# rcvr003.net
KiCad netlist of a schematic drawn in EAGLE
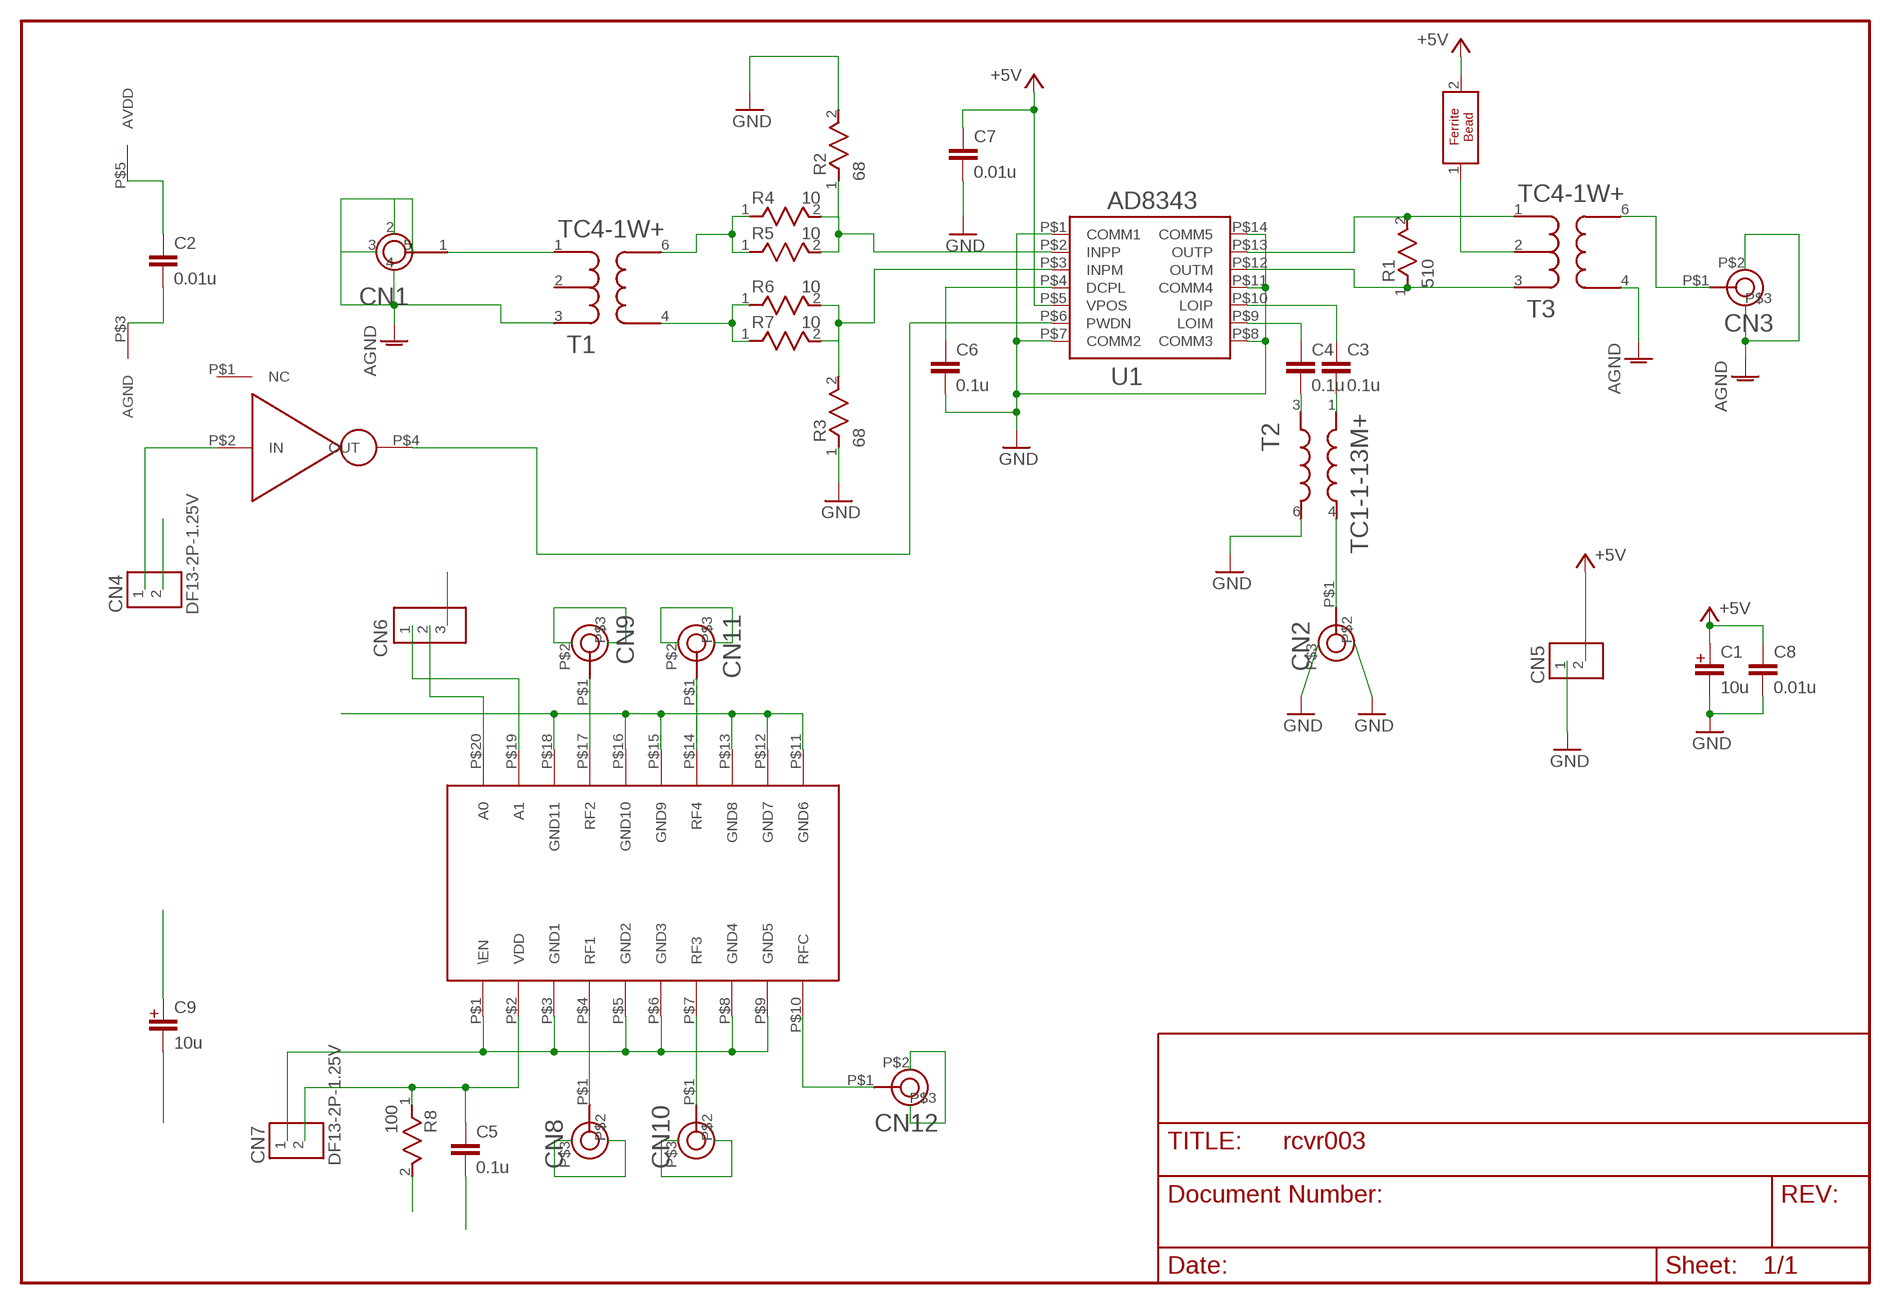
[diagram p0: schematic, sheet 1]

(export (version "E")
  (design (tool "Eeschema 10.0.6"))
  (components
    (comp (ref "C1")
      (value "10u")
      (footprint "eagle-import:3216_POLAR")
      (libsource (lib "eagle-import") (part "C_POLAR3216"))
    )
    (comp (ref "C2")
      (value "0.01u")
      (footprint "eagle-import:1005")
      (libsource (lib "eagle-import") (part "C1005"))
    )
    (comp (ref "C3")
      (value "0.1u")
      (footprint "eagle-import:1005")
      (libsource (lib "eagle-import") (part "C1005"))
    )
    (comp (ref "C4")
      (value "0.1u")
      (footprint "eagle-import:1005")
      (libsource (lib "eagle-import") (part "C1005"))
    )
    (comp (ref "C5")
      (value "0.1u")
      (footprint "eagle-import:1005")
      (libsource (lib "eagle-import") (part "C1005"))
    )
    (comp (ref "C6")
      (value "0.1u")
      (footprint "eagle-import:1005")
      (libsource (lib "eagle-import") (part "C1005"))
    )
    (comp (ref "C7")
      (value "0.01u")
      (footprint "eagle-import:1005")
      (libsource (lib "eagle-import") (part "C1005"))
    )
    (comp (ref "C8")
      (value "0.01u")
      (footprint "eagle-import:1608")
      (libsource (lib "eagle-import") (part "C1608"))
    )
    (comp (ref "C9")
      (value "10u")
      (footprint "eagle-import:3216_POLAR")
      (libsource (lib "eagle-import") (part "C_POLAR3216"))
    )
    (comp (ref "CN1")
      (value "SMASTRAIGHT")
      (footprint "eagle-import:SMA_STRAIGHT")
      (libsource (lib "eagle-import") (part "SMASTRAIGHT"))
    )
    (comp (ref "CN2")
      (value "U.FL-R-SMT")
      (footprint "eagle-import:U.FL-R-SMT")
      (libsource (lib "eagle-import") (part "U.FL-R-SMT"))
    )
    (comp (ref "CN3")
      (value "U.FL-R-SMT")
      (footprint "eagle-import:U.FL-R-SMT")
      (libsource (lib "eagle-import") (part "U.FL-R-SMT"))
    )
    (comp (ref "CN4")
      (value "DF13-2P-1.25V")
      (footprint "eagle-import:DF13-2P-12.5V")
      (libsource (lib "eagle-import") (part "DF13-2P-1.25V"))
    )
    (comp (ref "CN5")
      (value "DF13-2P-1.25V")
      (footprint "eagle-import:DF13-2P-12.5V")
      (libsource (lib "eagle-import") (part "DF13-2P-1.25V"))
    )
    (comp (ref "CN6")
      (value "DF13-3P-1.25V")
      (footprint "eagle-import:DF13-3P-1.25V")
      (libsource (lib "eagle-import") (part "DF13-3P-1.25V"))
    )
    (comp (ref "CN7")
      (value "DF13-2P-1.25V")
      (footprint "eagle-import:DF13-2P-12.5V")
      (libsource (lib "eagle-import") (part "DF13-2P-1.25V"))
    )
    (comp (ref "CN8")
      (value "U.FL-R-SMT")
      (footprint "eagle-import:U.FL-R-SMT")
      (libsource (lib "eagle-import") (part "U.FL-R-SMT"))
    )
    (comp (ref "CN9")
      (value "U.FL-R-SMT")
      (footprint "eagle-import:U.FL-R-SMT")
      (libsource (lib "eagle-import") (part "U.FL-R-SMT"))
    )
    (comp (ref "CN10")
      (value "U.FL-R-SMT")
      (footprint "eagle-import:U.FL-R-SMT")
      (libsource (lib "eagle-import") (part "U.FL-R-SMT"))
    )
    (comp (ref "CN11")
      (value "U.FL-R-SMT")
      (footprint "eagle-import:U.FL-R-SMT")
      (libsource (lib "eagle-import") (part "U.FL-R-SMT"))
    )
    (comp (ref "CN12")
      (value "U.FL-R-SMT")
      (footprint "eagle-import:U.FL-R-SMT")
      (libsource (lib "eagle-import") (part "U.FL-R-SMT"))
    )
    (comp (ref "FB2")
      (value "FERRITEBEAD")
      (footprint "eagle-import:1608")
      (libsource (lib "eagle-import") (part "FERRITEBEAD"))
    )
    (comp (ref "R1")
      (value "510")
      (footprint "eagle-import:1608")
      (libsource (lib "eagle-import") (part "R1608"))
    )
    (comp (ref "R2")
      (value "68")
      (footprint "eagle-import:1608")
      (libsource (lib "eagle-import") (part "R1608"))
    )
    (comp (ref "R3")
      (value "68")
      (footprint "eagle-import:1608")
      (libsource (lib "eagle-import") (part "R1608"))
    )
    (comp (ref "R4")
      (value "10")
      (footprint "eagle-import:1005")
      (libsource (lib "eagle-import") (part "R1005"))
    )
    (comp (ref "R5")
      (value "10")
      (footprint "eagle-import:1005")
      (libsource (lib "eagle-import") (part "R1005"))
    )
    (comp (ref "R6")
      (value "10")
      (footprint "eagle-import:1005")
      (libsource (lib "eagle-import") (part "R1005"))
    )
    (comp (ref "R7")
      (value "10")
      (footprint "eagle-import:1005")
      (libsource (lib "eagle-import") (part "R1005"))
    )
    (comp (ref "R8")
      (value "100")
      (footprint "eagle-import:1608")
      (libsource (lib "eagle-import") (part "R1608"))
    )
    (comp (ref "T1")
      (value "TC4-1W+")
      (footprint "eagle-import:AT224")
      (libsource (lib "eagle-import") (part "TC4-1W+"))
    )
    (comp (ref "T2")
      (value "TC1-1-13M+")
      (footprint "eagle-import:AT224")
      (libsource (lib "eagle-import") (part "TC1-1-13M+"))
    )
    (comp (ref "T3")
      (value "TC4-1W+")
      (footprint "eagle-import:AT224")
      (libsource (lib "eagle-import") (part "TC4-1W+"))
    )
    (comp (ref "U1")
      (value "AD8343")
      (footprint "eagle-import:AD8343")
      (libsource (lib "eagle-import") (part "AD8343"))
    )
    (comp (ref "U2")
      (value "MC74VHC1G04")
      (footprint "eagle-import:MC74VHC1G04")
      (libsource (lib "eagle-import") (part "MC74VHC1G04"))
    )
    (comp (ref "U3")
      (value "ADG904")
      (footprint "eagle-import:ADG904_TSSOP")
      (libsource (lib "eagle-import") (part "ADG904"))
    )
  )
  (nets
    (net (code "1") (name "+5V") (class "Default")
      (node (ref "C1") (pin "1") (pinfunction "1_1") (pintype "passive"))
      (node (ref "C2") (pin "1") (pinfunction "1_1") (pintype "passive"))
      (node (ref "C7") (pin "1") (pinfunction "1_1") (pintype "passive"))
      (node (ref "C8") (pin "1") (pinfunction "1_1") (pintype "passive"))
      (node (ref "CN5") (pin "2") (pinfunction "2_2") (pintype "bidirectional"))
      (node (ref "FB2") (pin "2") (pinfunction "P$4_2") (pintype "bidirectional"))
      (node (ref "U1") (pin "P$5") (pinfunction "VPOS_P$5") (pintype "power_in"))
      (node (ref "U2") (pin "P$5") (pinfunction "AVDD_P$5") (pintype "power_in"))
    )
    (net (code "2") (name "/3.3V") (class "Default")
      (node (ref "C5") (pin "1") (pinfunction "1_1") (pintype "passive"))
      (node (ref "C9") (pin "1") (pinfunction "1_1") (pintype "passive"))
      (node (ref "CN7") (pin "2") (pinfunction "2_2") (pintype "bidirectional"))
      (node (ref "R8") (pin "1") (pinfunction "1_1") (pintype "passive"))
      (node (ref "U3") (pin "P$2") (pinfunction "VDD_P$2") (pintype "bidirectional"))
    )
    (net (code "3") (name "/GND2") (class "Default")
      (node (ref "C5") (pin "2") (pinfunction "2_2") (pintype "passive"))
      (node (ref "C9") (pin "2") (pinfunction "2_2") (pintype "passive"))
      (node (ref "CN10") (pin "P$2") (pinfunction "AGND_P$2") (pintype "power_in"))
      (node (ref "CN10") (pin "P$3") (pinfunction "AGND2_P$3") (pintype "power_in"))
      (node (ref "CN11") (pin "P$2") (pinfunction "AGND_P$2") (pintype "power_in"))
      (node (ref "CN11") (pin "P$3") (pinfunction "AGND2_P$3") (pintype "power_in"))
      (node (ref "CN12") (pin "P$2") (pinfunction "AGND_P$2") (pintype "power_in"))
      (node (ref "CN12") (pin "P$3") (pinfunction "AGND2_P$3") (pintype "power_in"))
      (node (ref "CN7") (pin "1") (pinfunction "1_1") (pintype "bidirectional"))
      (node (ref "CN8") (pin "P$2") (pinfunction "AGND_P$2") (pintype "power_in"))
      (node (ref "CN8") (pin "P$3") (pinfunction "AGND2_P$3") (pintype "power_in"))
      (node (ref "CN9") (pin "P$2") (pinfunction "AGND_P$2") (pintype "power_in"))
      (node (ref "CN9") (pin "P$3") (pinfunction "AGND2_P$3") (pintype "power_in"))
      (node (ref "U3") (pin "P$1") (pinfunction "\\EN_P$1") (pintype "bidirectional"))
      (node (ref "U3") (pin "P$11") (pinfunction "GND6_P$11") (pintype "bidirectional"))
      (node (ref "U3") (pin "P$12") (pinfunction "GND7_P$12") (pintype "bidirectional"))
      (node (ref "U3") (pin "P$13") (pinfunction "GND8_P$13") (pintype "bidirectional"))
      (node (ref "U3") (pin "P$15") (pinfunction "GND9_P$15") (pintype "bidirectional"))
      (node (ref "U3") (pin "P$16") (pinfunction "GND10_P$16") (pintype "bidirectional"))
      (node (ref "U3") (pin "P$18") (pinfunction "GND11_P$18") (pintype "bidirectional"))
      (node (ref "U3") (pin "P$3") (pinfunction "GND1_P$3") (pintype "bidirectional"))
      (node (ref "U3") (pin "P$5") (pinfunction "GND2_P$5") (pintype "bidirectional"))
      (node (ref "U3") (pin "P$6") (pinfunction "GND3_P$6") (pintype "bidirectional"))
      (node (ref "U3") (pin "P$8") (pinfunction "GND4_P$8") (pintype "bidirectional"))
      (node (ref "U3") (pin "P$9") (pinfunction "GND5_P$9") (pintype "bidirectional"))
    )
    (net (code "4") (name "AGND") (class "Default")
      (node (ref "C1") (pin "2") (pinfunction "2_2") (pintype "passive"))
      (node (ref "C2") (pin "2") (pinfunction "2_2") (pintype "passive"))
      (node (ref "C6") (pin "2") (pinfunction "2_2") (pintype "passive"))
      (node (ref "C7") (pin "2") (pinfunction "2_2") (pintype "passive"))
      (node (ref "C8") (pin "2") (pinfunction "2_2") (pintype "passive"))
      (node (ref "CN1") (pin "2") (pinfunction "GND_2") (pintype "power_in"))
      (node (ref "CN1") (pin "3") (pinfunction "GND_3") (pintype "power_in"))
      (node (ref "CN1") (pin "4") (pinfunction "GND_4") (pintype "power_in"))
      (node (ref "CN1") (pin "5") (pinfunction "GND_5") (pintype "power_in"))
      (node (ref "CN2") (pin "P$2") (pinfunction "AGND_P$2") (pintype "power_in"))
      (node (ref "CN2") (pin "P$3") (pinfunction "AGND2_P$3") (pintype "power_in"))
      (node (ref "CN3") (pin "P$2") (pinfunction "AGND_P$2") (pintype "power_in"))
      (node (ref "CN3") (pin "P$3") (pinfunction "AGND2_P$3") (pintype "power_in"))
      (node (ref "CN4") (pin "2") (pinfunction "2_2") (pintype "bidirectional"))
      (node (ref "CN5") (pin "1") (pinfunction "1_1") (pintype "bidirectional"))
      (node (ref "R2") (pin "2") (pinfunction "2_2") (pintype "passive"))
      (node (ref "R3") (pin "1") (pinfunction "1_1") (pintype "passive"))
      (node (ref "T1") (pin "3") (pinfunction "3_3") (pintype "bidirectional"))
      (node (ref "T2") (pin "6") (pinfunction "4_6") (pintype "bidirectional"))
      (node (ref "T3") (pin "4") (pinfunction "4_4") (pintype "bidirectional"))
      (node (ref "U1") (pin "P$1") (pinfunction "COMM1_P$1") (pintype "power_in"))
      (node (ref "U1") (pin "P$11") (pinfunction "COMM4_P$11") (pintype "power_in"))
      (node (ref "U1") (pin "P$14") (pinfunction "COMM5_P$14") (pintype "power_in"))
      (node (ref "U1") (pin "P$7") (pinfunction "COMM2_P$7") (pintype "power_in"))
      (node (ref "U1") (pin "P$8") (pinfunction "COMM3_P$8") (pintype "power_in"))
      (node (ref "U2") (pin "P$3") (pinfunction "AGND_P$3") (pintype "power_in"))
    )
    (net (code "5") (name "Net-(C3-Pad2)") (class "Default")
      (node (ref "C3") (pin "2") (pinfunction "2_2") (pintype "passive"))
      (node (ref "T2") (pin "1") (pinfunction "1_1") (pintype "bidirectional"))
    )
    (net (code "6") (name "Net-(CN1-Pad1)") (class "Default")
      (node (ref "CN1") (pin "1") (pinfunction "1_1") (pintype "bidirectional"))
      (node (ref "T1") (pin "1") (pinfunction "1_1") (pintype "bidirectional"))
    )
    (net (code "7") (name "Net-(CN3-PadP$1)") (class "Default")
      (node (ref "CN3") (pin "P$1") (pinfunction "P$1_P$1") (pintype "bidirectional"))
      (node (ref "T3") (pin "6") (pinfunction "6_6") (pintype "bidirectional"))
    )
    (net (code "8") (name "Net-(FB2-P$3)") (class "Default")
      (node (ref "FB2") (pin "1") (pinfunction "P$3_1") (pintype "bidirectional"))
      (node (ref "T3") (pin "2") (pinfunction "2_2") (pintype "bidirectional"))
    )
    (net (code "9") (name "Net-(R4-Pad1)") (class "Default")
      (node (ref "R4") (pin "1") (pinfunction "1_1") (pintype "passive"))
      (node (ref "R5") (pin "1") (pinfunction "1_1") (pintype "passive"))
      (node (ref "T1") (pin "6") (pinfunction "6_6") (pintype "bidirectional"))
    )
    (net (code "10") (name "Net-(R6-Pad1)") (class "Default")
      (node (ref "R6") (pin "1") (pinfunction "1_1") (pintype "passive"))
      (node (ref "R7") (pin "1") (pinfunction "1_1") (pintype "passive"))
      (node (ref "T1") (pin "4") (pinfunction "4_4") (pintype "bidirectional"))
    )
    (net (code "11") (name "Net-(T2-2)") (class "Default")
      (node (ref "C4") (pin "2") (pinfunction "2_2") (pintype "passive"))
      (node (ref "T2") (pin "3") (pinfunction "2_3") (pintype "bidirectional"))
    )
    (net (code "12") (name "Net-(T2-3)") (class "Default")
      (node (ref "CN2") (pin "P$1") (pinfunction "P$1_P$1") (pintype "bidirectional"))
      (node (ref "T2") (pin "4") (pinfunction "3_4") (pintype "bidirectional"))
    )
    (net (code "13") (name "Net-(U1-DCPL)") (class "Default")
      (node (ref "C6") (pin "1") (pinfunction "1_1") (pintype "passive"))
      (node (ref "U1") (pin "P$4") (pinfunction "DCPL_P$4") (pintype "input"))
    )
    (net (code "14") (name "Net-(U1-INPM)") (class "Default")
      (node (ref "R3") (pin "2") (pinfunction "2_2") (pintype "passive"))
      (node (ref "R6") (pin "2") (pinfunction "2_2") (pintype "passive"))
      (node (ref "R7") (pin "2") (pinfunction "2_2") (pintype "passive"))
      (node (ref "U1") (pin "P$3") (pinfunction "INPM_P$3") (pintype "input"))
    )
    (net (code "15") (name "Net-(U1-INPP)") (class "Default")
      (node (ref "R2") (pin "1") (pinfunction "1_1") (pintype "passive"))
      (node (ref "R4") (pin "2") (pinfunction "2_2") (pintype "passive"))
      (node (ref "R5") (pin "2") (pinfunction "2_2") (pintype "passive"))
      (node (ref "U1") (pin "P$2") (pinfunction "INPP_P$2") (pintype "input"))
    )
    (net (code "16") (name "Net-(U1-LOIM)") (class "Default")
      (node (ref "C4") (pin "1") (pinfunction "1_1") (pintype "passive"))
      (node (ref "U1") (pin "P$9") (pinfunction "LOIM_P$9") (pintype "input"))
    )
    (net (code "17") (name "Net-(U1-LOIP)") (class "Default")
      (node (ref "C3") (pin "1") (pinfunction "1_1") (pintype "passive"))
      (node (ref "U1") (pin "P$10") (pinfunction "LOIP_P$10") (pintype "input"))
    )
    (net (code "18") (name "Net-(U1-OUTM)") (class "Default")
      (node (ref "R1") (pin "1") (pinfunction "1_1") (pintype "passive"))
      (node (ref "T3") (pin "3") (pinfunction "3_3") (pintype "bidirectional"))
      (node (ref "U1") (pin "P$12") (pinfunction "OUTM_P$12") (pintype "output"))
    )
    (net (code "19") (name "Net-(U1-OUTP)") (class "Default")
      (node (ref "R1") (pin "2") (pinfunction "2_2") (pintype "passive"))
      (node (ref "T3") (pin "1") (pinfunction "1_1") (pintype "bidirectional"))
      (node (ref "U1") (pin "P$13") (pinfunction "OUTP_P$13") (pintype "output"))
    )
    (net (code "20") (name "Net-(U1-PWDN)") (class "Default")
      (node (ref "U1") (pin "P$6") (pinfunction "PWDN_P$6") (pintype "input"))
      (node (ref "U2") (pin "P$4") (pinfunction "OUT_P$4") (pintype "bidirectional"))
    )
    (net (code "21") (name "Net-(U2A-IN)") (class "Default")
      (node (ref "CN4") (pin "1") (pinfunction "1_1") (pintype "bidirectional"))
      (node (ref "U2") (pin "P$2") (pinfunction "IN_P$2") (pintype "bidirectional"))
    )
    (net (code "22") (name "Net-(U3-A0)") (class "Default")
      (node (ref "CN6") (pin "2") (pinfunction "2_2") (pintype "bidirectional"))
      (node (ref "U3") (pin "P$20") (pinfunction "A0_P$20") (pintype "bidirectional"))
    )
    (net (code "23") (name "Net-(U3-A1)") (class "Default")
      (node (ref "CN6") (pin "1") (pinfunction "1_1") (pintype "bidirectional"))
      (node (ref "U3") (pin "P$19") (pinfunction "A1_P$19") (pintype "bidirectional"))
    )
    (net (code "24") (name "Net-(U3-RF1)") (class "Default")
      (node (ref "CN8") (pin "P$1") (pinfunction "P$1_P$1") (pintype "bidirectional"))
      (node (ref "U3") (pin "P$4") (pinfunction "RF1_P$4") (pintype "bidirectional"))
    )
    (net (code "25") (name "Net-(U3-RF2)") (class "Default")
      (node (ref "CN9") (pin "P$1") (pinfunction "P$1_P$1") (pintype "bidirectional"))
      (node (ref "U3") (pin "P$17") (pinfunction "RF2_P$17") (pintype "bidirectional"))
    )
    (net (code "26") (name "Net-(U3-RF3)") (class "Default")
      (node (ref "CN10") (pin "P$1") (pinfunction "P$1_P$1") (pintype "bidirectional"))
      (node (ref "U3") (pin "P$7") (pinfunction "RF3_P$7") (pintype "bidirectional"))
    )
    (net (code "27") (name "Net-(U3-RF4)") (class "Default")
      (node (ref "CN11") (pin "P$1") (pinfunction "P$1_P$1") (pintype "bidirectional"))
      (node (ref "U3") (pin "P$14") (pinfunction "RF4_P$14") (pintype "bidirectional"))
    )
    (net (code "28") (name "Net-(U3-RFC)") (class "Default")
      (node (ref "CN12") (pin "P$1") (pinfunction "P$1_P$1") (pintype "bidirectional"))
      (node (ref "U3") (pin "P$10") (pinfunction "RFC_P$10") (pintype "bidirectional"))
    )
    (net (code "29") (name "unconnected-(CN6-Pad3)") (class "Default")
      (node (ref "CN6") (pin "3") (pinfunction "3_3") (pintype "bidirectional"))
    )
    (net (code "30") (name "unconnected-(R8-Pad2)") (class "Default")
      (node (ref "R8") (pin "2") (pinfunction "2_2") (pintype "passive"))
    )
    (net (code "31") (name "unconnected-(T1-Pad2)") (class "Default")
      (node (ref "T1") (pin "2") (pinfunction "2_2") (pintype "bidirectional"))
    )
    (net (code "32") (name "unconnected-(U2A-NC-PadP$1)") (class "Default")
      (node (ref "U2") (pin "P$1") (pinfunction "NC_P$1") (pintype "bidirectional"))
    )
  )
)
